# OSO-SWAT-A1-04-BLUE.net
KiCad netlist of a schematic drawn in EAGLE
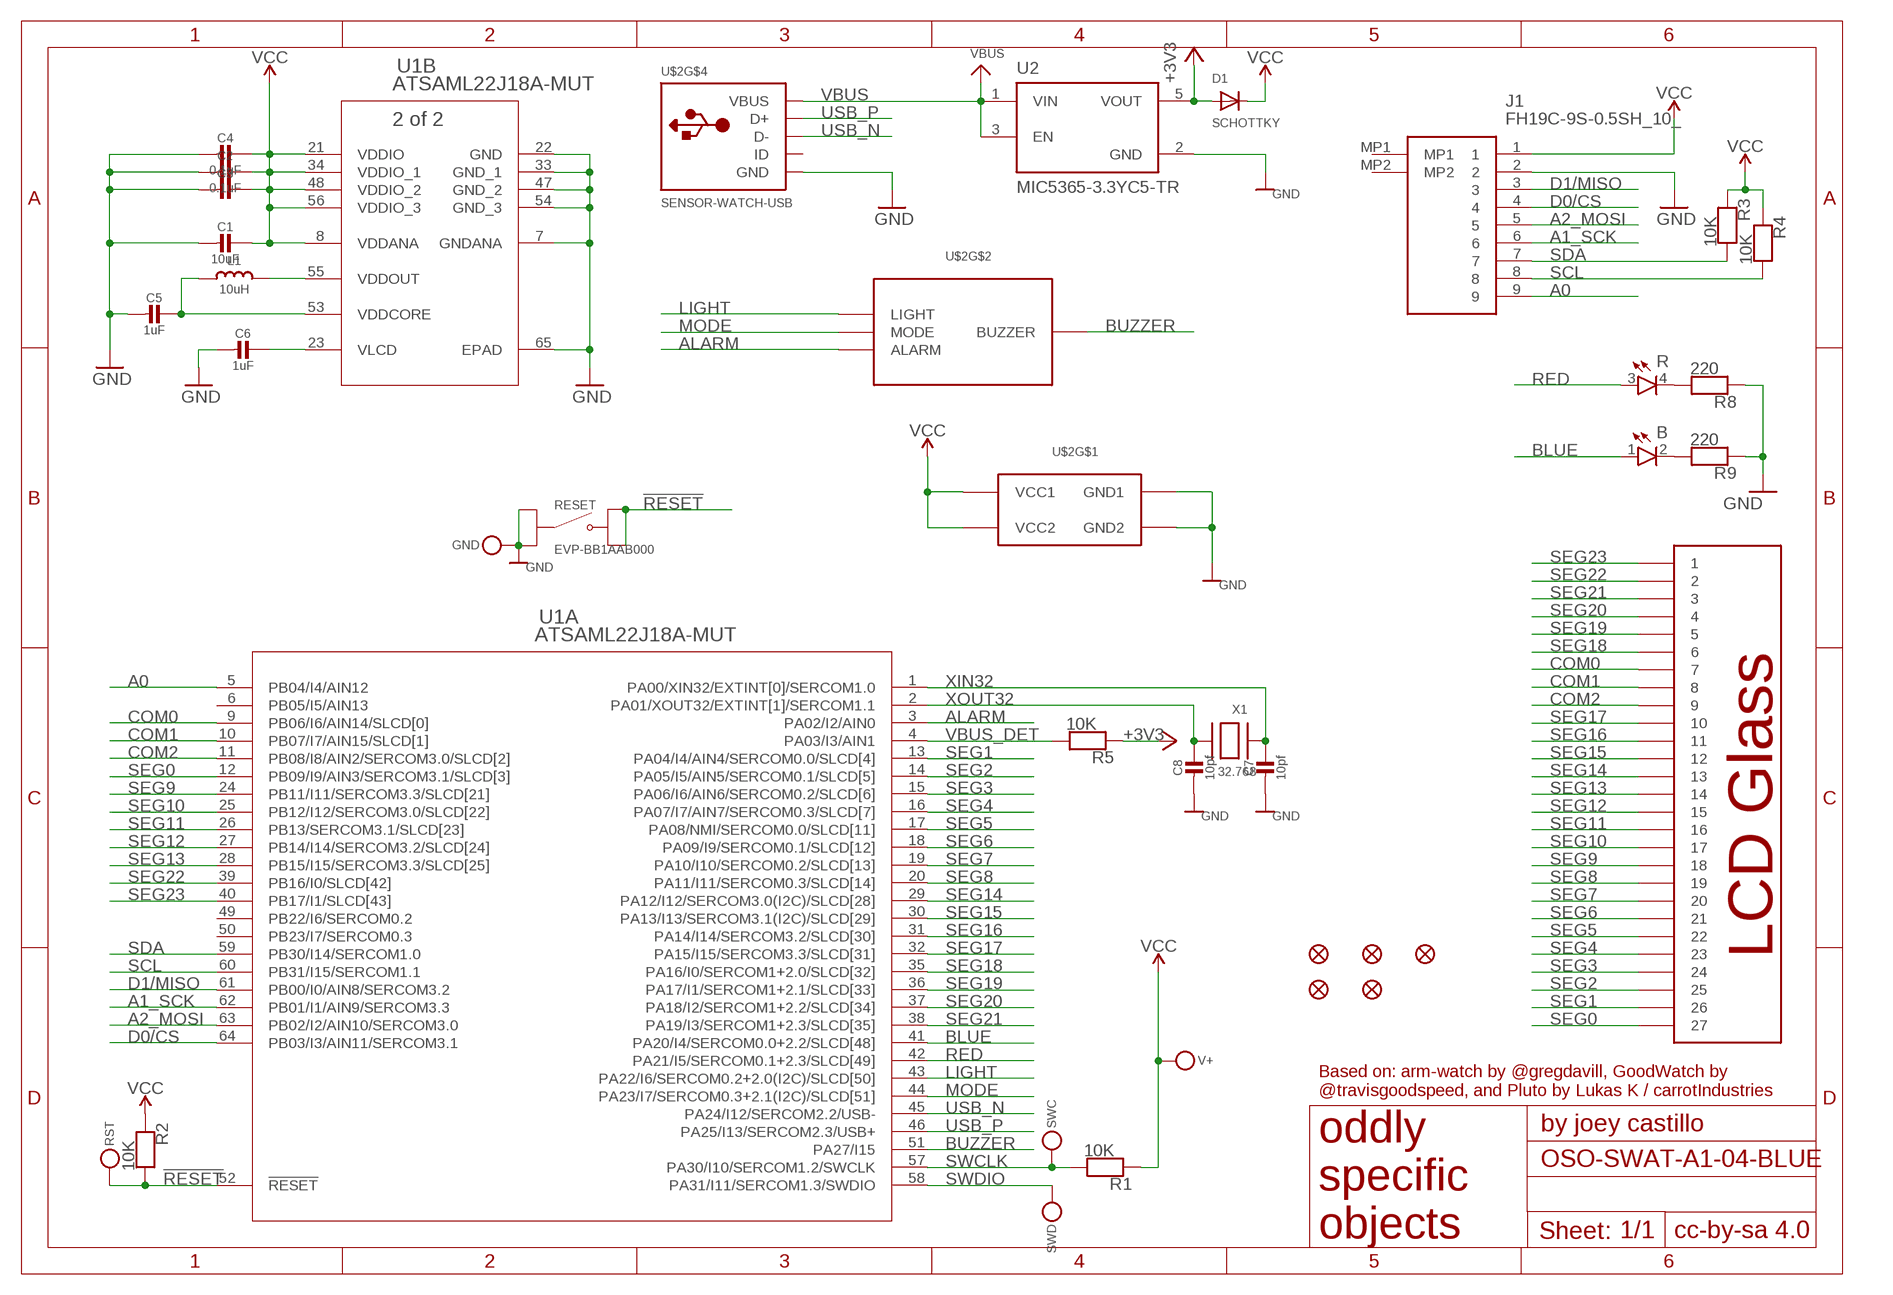
[diagram p0: schematic, sheet 1]

(export (version "E")
  (design (tool "Eeschema 10.0.6"))
  (components
    (comp (ref "C1")
      (value "10uF")
      (footprint "eagle-import:_0603MP")
      (libsource (lib "eagle-import") (part "CAP_CERAMIC_0603MP"))
    )
    (comp (ref "C2")
      (value "0.1uF")
      (footprint "eagle-import:_0603MP")
      (libsource (lib "eagle-import") (part "CAP_CERAMIC_0603MP"))
    )
    (comp (ref "C3")
      (value "0.1uF")
      (footprint "eagle-import:_0603MP")
      (libsource (lib "eagle-import") (part "CAP_CERAMIC_0603MP"))
    )
    (comp (ref "C4")
      (value "0.1uF")
      (footprint "eagle-import:_0603MP")
      (libsource (lib "eagle-import") (part "CAP_CERAMIC_0603MP"))
    )
    (comp (ref "C5")
      (value "1uF")
      (footprint "eagle-import:_0603MP")
      (libsource (lib "eagle-import") (part "CAP_CERAMIC_0603MP"))
    )
    (comp (ref "C6")
      (value "1uF")
      (footprint "eagle-import:_0603MP")
      (libsource (lib "eagle-import") (part "CAP_CERAMIC_0603MP"))
    )
    (comp (ref "C7")
      (value "10pf")
      (footprint "eagle-import:_0402MP")
      (libsource (lib "eagle-import") (part "CAP_CERAMIC_0402MP"))
    )
    (comp (ref "C8")
      (value "10pf")
      (footprint "eagle-import:_0402MP")
      (libsource (lib "eagle-import") (part "CAP_CERAMIC_0402MP"))
    )
    (comp (ref "D1")
      (value "SCHOTTKY")
      (footprint "eagle-import:SOD-323F")
      (libsource (lib "eagle-import") (part "DIODESOD-323F"))
    )
    (comp (ref "FID1")
      (value "FIDUCIAL_1MM")
      (footprint "eagle-import:FIDUCIAL_1MM")
      (libsource (lib "eagle-import") (part "FIDUCIAL_1MM"))
    )
    (comp (ref "FID2")
      (value "FIDUCIAL_1MM")
      (footprint "eagle-import:FIDUCIAL_1MM")
      (libsource (lib "eagle-import") (part "FIDUCIAL_1MM"))
    )
    (comp (ref "FID3")
      (value "FIDUCIAL_1MM")
      (footprint "eagle-import:FIDUCIAL_1MM")
      (fields (field (name "REV") "A"))
      (libsource (lib "eagle-import") (part "FIDUCIAL_1MM"))
    )
    (comp (ref "FID4")
      (value "FIDUCIAL_1MM")
      (footprint "eagle-import:FIDUCIAL_1MM")
      (libsource (lib "eagle-import") (part "FIDUCIAL_1MM"))
    )
    (comp (ref "FID6")
      (value "FIDUCIAL_1MM")
      (footprint "eagle-import:FIDUCIAL_1MM")
      (fields (field (name "REV") "A"))
      (libsource (lib "eagle-import") (part "FIDUCIAL_1MM"))
    )
    (comp (ref "GND")
      (value "MICROBUILDER_TESTPOINTROUND1.5MM")
      (footprint "eagle-import:MICROBUILDER_TESTPOINT_ROUND_1.5MM")
      (libsource (lib "eagle-import") (part "MICROBUILDER_TESTPOINTROUND1.5MM"))
    )
    (comp (ref "J1")
      (value "FH19C-9S-0.5SH_10_")
      (footprint "eagle-import:FH19C9S05SH10")
      (fields
        (field (name "MANUFACTURER_PART_NUMBER") "FH19C-9S-0.5SH(10)")
        (field (name "MOUSER_PART_NUMBER") "798-FH19C9S05SH10")
      )
      (libsource (lib "eagle-import") (part "FH19C-9S-0.5SH_10_"))
    )
    (comp (ref "L1")
      (value "10uH")
      (footprint "eagle-import:MICROBUILDER__0805MP")
      (libsource (lib "eagle-import") (part "MICROBUILDER_INDUCTOR_0805MP"))
    )
    (comp (ref "LED")
      (value "QBLP655-RIB")
      (footprint "eagle-import:LED_QBLP655")
      (fields
        (field (name "DIGI-KEY_PART_NUMBER") "160-2026-1-ND")
        (field (name "MF") "Lite-On Inc.")
        (field (name "MP") "LTST-C235KGKRKT")
      )
      (libsource (lib "eagle-import") (part "QBLP655-RIB"))
    )
    (comp (ref "R1")
      (value "10K")
      (footprint "eagle-import:_0603MP")
      (libsource (lib "eagle-import") (part "RESISTOR_0603MP"))
    )
    (comp (ref "R2")
      (value "10K")
      (footprint "eagle-import:_0603MP")
      (libsource (lib "eagle-import") (part "RESISTOR_0603MP"))
    )
    (comp (ref "R3")
      (value "10K")
      (footprint "eagle-import:_0603MP")
      (libsource (lib "eagle-import") (part "RESISTOR_0603MP"))
    )
    (comp (ref "R4")
      (value "10K")
      (footprint "eagle-import:_0603MP")
      (libsource (lib "eagle-import") (part "RESISTOR_0603MP"))
    )
    (comp (ref "R5")
      (value "10K")
      (footprint "eagle-import:_0603MP")
      (libsource (lib "eagle-import") (part "RESISTOR_0603MP"))
    )
    (comp (ref "R8")
      (value "220")
      (footprint "eagle-import:_0603MP")
      (libsource (lib "eagle-import") (part "RESISTOR_0603MP"))
    )
    (comp (ref "R9")
      (value "220")
      (footprint "eagle-import:_0603MP")
      (libsource (lib "eagle-import") (part "RESISTOR_0603MP"))
    )
    (comp (ref "RESET")
      (value "EVP-BB1AAB000")
      (footprint "eagle-import:SW_EVP-BB1AAB000")
      (fields
        (field (name "DIGI-KEY_PART_NUMBER") "P124390CT-ND")
        (field (name "MF") "Panasonic Electronic Components")
      )
      (libsource (lib "eagle-import") (part "EVP-BB1AAB000"))
    )
    (comp (ref "RST")
      (value "MICROBUILDER_TESTPOINTROUND1.5MM")
      (footprint "eagle-import:MICROBUILDER_TESTPOINT_ROUND_1.5MM")
      (libsource (lib "eagle-import") (part "MICROBUILDER_TESTPOINTROUND1.5MM"))
    )
    (comp (ref "SWC")
      (value "MICROBUILDER_TESTPOINTROUND1.5MM")
      (footprint "eagle-import:MICROBUILDER_TESTPOINT_ROUND_1.5MM")
      (libsource (lib "eagle-import") (part "MICROBUILDER_TESTPOINTROUND1.5MM"))
    )
    (comp (ref "SWD")
      (value "MICROBUILDER_TESTPOINTROUND1.5MM")
      (footprint "eagle-import:MICROBUILDER_TESTPOINT_ROUND_1.5MM")
      (libsource (lib "eagle-import") (part "MICROBUILDER_TESTPOINTROUND1.5MM"))
    )
    (comp (ref "U$2")
      (value "SENSOR-WATCH-USB")
      (footprint "eagle-import:CASIO-F91W-OUTLINE-USB")
      (libsource (lib "eagle-import") (part "SENSOR-WATCH-USB"))
    )
    (comp (ref "U1")
      (value "ATSAML22J18A-MUT")
      (footprint "eagle-import:QFN64_9X9MC_MCH")
      (fields (field (name "COPYRIGHT") "Copyright (C) 2018 Accelerated Designs. All rights reserved"))
      (libsource (lib "eagle-import") (part "ATSAML22J18A-MUT"))
    )
    (comp (ref "U2")
      (value "MIC5365-3.3YC5-TR")
      (footprint "eagle-import:SOT65P210X110-5N")
      (fields (field (name "DIGI-KEY_PART_NUMBER") "576-3193-1-ND") (field (name "MF") "Microchip"))
      (libsource (lib "eagle-import") (part "MIC5365-3.3YC5-TR"))
    )
    (comp (ref "V+")
      (value "MICROBUILDER_TESTPOINTROUND1.5MM")
      (footprint "eagle-import:MICROBUILDER_TESTPOINT_ROUND_1.5MM")
      (libsource (lib "eagle-import") (part "MICROBUILDER_TESTPOINTROUND1.5MM"))
    )
    (comp (ref "X1")
      (value "32.768")
      (footprint "eagle-import:XTAL3215")
      (libsource (lib "eagle-import") (part "XTAL-3.2X1.5"))
    )
  )
  (nets
    (net (code "1") (name "+3V3") (class "Default")
      (node (ref "D1") (pin "A") (pinfunction "A_A") (pintype "passive"))
      (node (ref "R5") (pin "1") (pinfunction "1_1") (pintype "passive"))
      (node (ref "U2") (pin "5") (pinfunction "VOUT_5") (pintype "output"))
    )
    (net (code "2") (name "/A0") (class "Default")
      (node (ref "J1") (pin "9") (pinfunction "9_9") (pintype "bidirectional"))
      (node (ref "U1") (pin "5") (pinfunction "PB04/I4/AIN12_5") (pintype "bidirectional"))
    )
    (net (code "3") (name "/A1_SCK") (class "Default")
      (node (ref "J1") (pin "6") (pinfunction "6_6") (pintype "bidirectional"))
      (node (ref "U1") (pin "62") (pinfunction "PB01/I1/AIN9/SERCOM3.3_62") (pintype "bidirectional"))
    )
    (net (code "4") (name "/A2_MOSI") (class "Default")
      (node (ref "J1") (pin "5") (pinfunction "5_5") (pintype "bidirectional"))
      (node (ref "U1") (pin "63") (pinfunction "PB02/I2/AIN10/SERCOM3.0_63") (pintype "bidirectional"))
    )
    (net (code "5") (name "/ALARM") (class "Default")
      (node (ref "U$2") (pin "ALARM") (pinfunction "ALARM_ALARM") (pintype "bidirectional"))
      (node (ref "U1") (pin "3") (pinfunction "PA02/I2/AIN0_3") (pintype "bidirectional"))
    )
    (net (code "6") (name "/BLUE") (class "Default")
      (node (ref "LED") (pin "1") (pinfunction "A_1") (pintype "passive"))
      (node (ref "U1") (pin "41") (pinfunction "PA20/I4/SERCOM0.0+2.2/SLCD[48]_41") (pintype "bidirectional"))
    )
    (net (code "7") (name "/BUZZER") (class "Default")
      (node (ref "U$2") (pin "BUZZER") (pinfunction "BUZZER_BUZZER") (pintype "bidirectional"))
      (node (ref "U1") (pin "51") (pinfunction "PA27/I15_51") (pintype "bidirectional"))
    )
    (net (code "8") (name "/COM0") (class "Default")
      (node (ref "U$2") (pin "7") (pinfunction "7_7") (pintype "input"))
      (node (ref "U1") (pin "9") (pinfunction "PB06/I6/AIN14/SLCD[0]_9") (pintype "bidirectional"))
    )
    (net (code "9") (name "/COM1") (class "Default")
      (node (ref "U$2") (pin "8") (pinfunction "8_8") (pintype "input"))
      (node (ref "U1") (pin "10") (pinfunction "PB07/I7/AIN15/SLCD[1]_10") (pintype "bidirectional"))
    )
    (net (code "10") (name "/COM2") (class "Default")
      (node (ref "U$2") (pin "9") (pinfunction "9_9") (pintype "input"))
      (node (ref "U1") (pin "11") (pinfunction "PB08/I8/AIN2/SERCOM3.0/SLCD[2]_11") (pintype "bidirectional"))
    )
    (net (code "11") (name "/D0{slash}CS") (class "Default")
      (node (ref "J1") (pin "4") (pinfunction "4_4") (pintype "bidirectional"))
      (node (ref "U1") (pin "64") (pinfunction "PB03/I3/AIN11/SERCOM3.1_64") (pintype "bidirectional"))
    )
    (net (code "12") (name "/D1{slash}MISO") (class "Default")
      (node (ref "J1") (pin "3") (pinfunction "3_3") (pintype "bidirectional"))
      (node (ref "U1") (pin "61") (pinfunction "PB00/I0/AIN8/SERCOM3.2_61") (pintype "bidirectional"))
    )
    (net (code "13") (name "/LIGHT") (class "Default")
      (node (ref "U$2") (pin "LIGHT") (pinfunction "LIGHT_LIGHT") (pintype "bidirectional"))
      (node (ref "U1") (pin "43") (pinfunction "PA22/I6/SERCOM0.2+2.0(I2C)/SLCD[50]_43") (pintype "bidirectional"))
    )
    (net (code "14") (name "/MODE") (class "Default")
      (node (ref "U$2") (pin "MODE") (pinfunction "MODE_MODE") (pintype "bidirectional"))
      (node (ref "U1") (pin "44") (pinfunction "PA23/I7/SERCOM0.3+2.1(I2C)/SLCD[51]_44") (pintype "bidirectional"))
    )
    (net (code "15") (name "/RED") (class "Default")
      (node (ref "LED") (pin "3") (pinfunction "A_3") (pintype "passive"))
      (node (ref "U1") (pin "42") (pinfunction "PA21/I5/SERCOM0.1+2.3/SLCD[49]_42") (pintype "bidirectional"))
    )
    (net (code "16") (name "/SCL") (class "Default")
      (node (ref "J1") (pin "8") (pinfunction "8_8") (pintype "bidirectional"))
      (node (ref "R4") (pin "2") (pinfunction "2_2") (pintype "passive"))
      (node (ref "U1") (pin "60") (pinfunction "PB31/I15/SERCOM1.1_60") (pintype "bidirectional"))
    )
    (net (code "17") (name "/SDA") (class "Default")
      (node (ref "J1") (pin "7") (pinfunction "7_7") (pintype "bidirectional"))
      (node (ref "R3") (pin "2") (pinfunction "2_2") (pintype "passive"))
      (node (ref "U1") (pin "59") (pinfunction "PB30/I14/SERCOM1.0_59") (pintype "bidirectional"))
    )
    (net (code "18") (name "/SEG0") (class "Default")
      (node (ref "U$2") (pin "27") (pinfunction "27_27") (pintype "input"))
      (node (ref "U1") (pin "12") (pinfunction "PB09/I9/AIN3/SERCOM3.1/SLCD[3]_12") (pintype "bidirectional"))
    )
    (net (code "19") (name "/SEG1") (class "Default")
      (node (ref "U$2") (pin "26") (pinfunction "26_26") (pintype "input"))
      (node (ref "U1") (pin "13") (pinfunction "PA04/I4/AIN4/SERCOM0.0/SLCD[4]_13") (pintype "bidirectional"))
    )
    (net (code "20") (name "/SEG2") (class "Default")
      (node (ref "U$2") (pin "25") (pinfunction "25_25") (pintype "input"))
      (node (ref "U1") (pin "14") (pinfunction "PA05/I5/AIN5/SERCOM0.1/SLCD[5]_14") (pintype "bidirectional"))
    )
    (net (code "21") (name "/SEG3") (class "Default")
      (node (ref "U$2") (pin "24") (pinfunction "24_24") (pintype "input"))
      (node (ref "U1") (pin "15") (pinfunction "PA06/I6/AIN6/SERCOM0.2/SLCD[6]_15") (pintype "bidirectional"))
    )
    (net (code "22") (name "/SEG4") (class "Default")
      (node (ref "U$2") (pin "23") (pinfunction "23_23") (pintype "input"))
      (node (ref "U1") (pin "16") (pinfunction "PA07/I7/AIN7/SERCOM0.3/SLCD[7]_16") (pintype "bidirectional"))
    )
    (net (code "23") (name "/SEG5") (class "Default")
      (node (ref "U$2") (pin "22") (pinfunction "22_22") (pintype "input"))
      (node (ref "U1") (pin "17") (pinfunction "PA08/NMI/SERCOM0.0/SLCD[11]_17") (pintype "bidirectional"))
    )
    (net (code "24") (name "/SEG6") (class "Default")
      (node (ref "U$2") (pin "21") (pinfunction "21_21") (pintype "input"))
      (node (ref "U1") (pin "18") (pinfunction "PA09/I9/SERCOM0.1/SLCD[12]_18") (pintype "bidirectional"))
    )
    (net (code "25") (name "/SEG7") (class "Default")
      (node (ref "U$2") (pin "20") (pinfunction "20_20") (pintype "input"))
      (node (ref "U1") (pin "19") (pinfunction "PA10/I10/SERCOM0.2/SLCD[13]_19") (pintype "bidirectional"))
    )
    (net (code "26") (name "/SEG8") (class "Default")
      (node (ref "U$2") (pin "19") (pinfunction "19_19") (pintype "input"))
      (node (ref "U1") (pin "20") (pinfunction "PA11/I11/SERCOM0.3/SLCD[14]_20") (pintype "bidirectional"))
    )
    (net (code "27") (name "/SEG9") (class "Default")
      (node (ref "U$2") (pin "18") (pinfunction "18_18") (pintype "input"))
      (node (ref "U1") (pin "24") (pinfunction "PB11/I11/SERCOM3.3/SLCD[21]_24") (pintype "bidirectional"))
    )
    (net (code "28") (name "/SEG10") (class "Default")
      (node (ref "U$2") (pin "17") (pinfunction "17_17") (pintype "input"))
      (node (ref "U1") (pin "25") (pinfunction "PB12/I12/SERCOM3.0/SLCD[22]_25") (pintype "bidirectional"))
    )
    (net (code "29") (name "/SEG11") (class "Default")
      (node (ref "U$2") (pin "16") (pinfunction "16_16") (pintype "input"))
      (node (ref "U1") (pin "26") (pinfunction "PB13/SERCOM3.1/SLCD[23]_26") (pintype "bidirectional"))
    )
    (net (code "30") (name "/SEG12") (class "Default")
      (node (ref "U$2") (pin "15") (pinfunction "15_15") (pintype "input"))
      (node (ref "U1") (pin "27") (pinfunction "PB14/I14/SERCOM3.2/SLCD[24]_27") (pintype "bidirectional"))
    )
    (net (code "31") (name "/SEG13") (class "Default")
      (node (ref "U$2") (pin "14") (pinfunction "14_14") (pintype "input"))
      (node (ref "U1") (pin "28") (pinfunction "PB15/I15/SERCOM3.3/SLCD[25]_28") (pintype "bidirectional"))
    )
    (net (code "32") (name "/SEG14") (class "Default")
      (node (ref "U$2") (pin "13") (pinfunction "13_13") (pintype "input"))
      (node (ref "U1") (pin "29") (pinfunction "PA12/I12/SERCOM3.0(I2C)/SLCD[28]_29") (pintype "bidirectional"))
    )
    (net (code "33") (name "/SEG15") (class "Default")
      (node (ref "U$2") (pin "12") (pinfunction "12_12") (pintype "input"))
      (node (ref "U1") (pin "30") (pinfunction "PA13/I13/SERCOM3.1(I2C)/SLCD[29]_30") (pintype "bidirectional"))
    )
    (net (code "34") (name "/SEG16") (class "Default")
      (node (ref "U$2") (pin "11") (pinfunction "11_11") (pintype "input"))
      (node (ref "U1") (pin "31") (pinfunction "PA14/I14/SERCOM3.2/SLCD[30]_31") (pintype "bidirectional"))
    )
    (net (code "35") (name "/SEG17") (class "Default")
      (node (ref "U$2") (pin "10") (pinfunction "10_10") (pintype "input"))
      (node (ref "U1") (pin "32") (pinfunction "PA15/I15/SERCOM3.3/SLCD[31]_32") (pintype "bidirectional"))
    )
    (net (code "36") (name "/SEG18") (class "Default")
      (node (ref "U$2") (pin "6") (pinfunction "6_6") (pintype "input"))
      (node (ref "U1") (pin "35") (pinfunction "PA16/I0/SERCOM1+2.0/SLCD[32]_35") (pintype "bidirectional"))
    )
    (net (code "37") (name "/SEG19") (class "Default")
      (node (ref "U$2") (pin "5") (pinfunction "5_5") (pintype "input"))
      (node (ref "U1") (pin "36") (pinfunction "PA17/I1/SERCOM1+2.1/SLCD[33]_36") (pintype "bidirectional"))
    )
    (net (code "38") (name "/SEG20") (class "Default")
      (node (ref "U$2") (pin "4") (pinfunction "4_4") (pintype "input"))
      (node (ref "U1") (pin "37") (pinfunction "PA18/I2/SERCOM1+2.2/SLCD[34]_37") (pintype "bidirectional"))
    )
    (net (code "39") (name "/SEG21") (class "Default")
      (node (ref "U$2") (pin "3") (pinfunction "3_3") (pintype "input"))
      (node (ref "U1") (pin "38") (pinfunction "PA19/I3/SERCOM1+2.3/SLCD[35]_38") (pintype "bidirectional"))
    )
    (net (code "40") (name "/SEG22") (class "Default")
      (node (ref "U$2") (pin "2") (pinfunction "2_2") (pintype "input"))
      (node (ref "U1") (pin "39") (pinfunction "PB16/I0/SLCD[42]_39") (pintype "bidirectional"))
    )
    (net (code "41") (name "/SEG23") (class "Default")
      (node (ref "U$2") (pin "1") (pinfunction "1_1") (pintype "input"))
      (node (ref "U1") (pin "40") (pinfunction "PB17/I1/SLCD[43]_40") (pintype "bidirectional"))
    )
    (net (code "42") (name "/SWCLK") (class "Default")
      (node (ref "R1") (pin "2") (pinfunction "2_2") (pintype "passive"))
      (node (ref "SWC") (pin "P$1") (pinfunction "P$1_P$1") (pintype "bidirectional"))
      (node (ref "U1") (pin "57") (pinfunction "PA30/I10/SERCOM1.2/SWCLK_57") (pintype "bidirectional"))
    )
    (net (code "43") (name "/SWDIO") (class "Default")
      (node (ref "SWD") (pin "P$1") (pinfunction "P$1_P$1") (pintype "bidirectional"))
      (node (ref "U1") (pin "58") (pinfunction "PA31/I11/SERCOM1.3/SWDIO_58") (pintype "bidirectional"))
    )
    (net (code "44") (name "/USB_N") (class "Default")
      (node (ref "U$2") (pin "USB_N") (pinfunction "D-_USB_N") (pintype "bidirectional"))
      (node (ref "U1") (pin "45") (pinfunction "PA24/I12/SERCOM2.2/USB-_45") (pintype "bidirectional"))
    )
    (net (code "45") (name "/USB_P") (class "Default")
      (node (ref "U$2") (pin "USB_P") (pinfunction "D+_USB_P") (pintype "bidirectional"))
      (node (ref "U1") (pin "46") (pinfunction "PA25/I13/SERCOM2.3/USB+_46") (pintype "bidirectional"))
    )
    (net (code "46") (name "/VBUS_DET") (class "Default")
      (node (ref "R5") (pin "2") (pinfunction "2_2") (pintype "passive"))
      (node (ref "U1") (pin "4") (pinfunction "PA03/I3/AIN1_4") (pintype "bidirectional"))
    )
    (net (code "47") (name "/XIN32") (class "Default")
      (node (ref "C7") (pin "1") (pinfunction "1_1") (pintype "passive"))
      (node (ref "U1") (pin "1") (pinfunction "PA00/XIN32/EXTINT[0]/SERCOM1.0_1") (pintype "bidirectional"))
      (node (ref "X1") (pin "P$1") (pinfunction "P$1_P$1") (pintype "bidirectional"))
    )
    (net (code "48") (name "/XOUT32") (class "Default")
      (node (ref "C8") (pin "1") (pinfunction "1_1") (pintype "passive"))
      (node (ref "U1") (pin "2") (pinfunction "PA01/XOUT32/EXTINT[1]/SERCOM1.1_2") (pintype "bidirectional"))
      (node (ref "X1") (pin "P$2") (pinfunction "P$2_P$2") (pintype "bidirectional"))
    )
    (net (code "49") (name "/~{RESET}") (class "Default")
      (node (ref "R2") (pin "2") (pinfunction "2_2") (pintype "passive"))
      (node (ref "RESET") (pin "B1") (pinfunction "B1_B1") (pintype "passive"))
      (node (ref "RESET") (pin "B2") (pinfunction "B2_B2") (pintype "passive"))
      (node (ref "RST") (pin "P$1") (pinfunction "P$1_P$1") (pintype "bidirectional"))
      (node (ref "U1") (pin "52") (pinfunction "~{RESET}_52") (pintype "bidirectional"))
    )
    (net (code "50") (name "GND") (class "Default")
      (node (ref "C1") (pin "2") (pinfunction "2_2") (pintype "passive"))
      (node (ref "C2") (pin "2") (pinfunction "2_2") (pintype "passive"))
      (node (ref "C3") (pin "2") (pinfunction "2_2") (pintype "passive"))
      (node (ref "C4") (pin "2") (pinfunction "2_2") (pintype "passive"))
      (node (ref "C5") (pin "2") (pinfunction "2_2") (pintype "passive"))
      (node (ref "C6") (pin "2") (pinfunction "2_2") (pintype "passive"))
      (node (ref "C7") (pin "2") (pinfunction "2_2") (pintype "passive"))
      (node (ref "C8") (pin "2") (pinfunction "2_2") (pintype "passive"))
      (node (ref "GND") (pin "P$1") (pinfunction "P$1_P$1") (pintype "bidirectional"))
      (node (ref "J1") (pin "2") (pinfunction "2_2") (pintype "bidirectional"))
      (node (ref "R8") (pin "1") (pinfunction "1_1") (pintype "passive"))
      (node (ref "R9") (pin "1") (pinfunction "1_1") (pintype "passive"))
      (node (ref "RESET") (pin "A1") (pinfunction "A1_A1") (pintype "passive"))
      (node (ref "RESET") (pin "A2") (pinfunction "A2_A2") (pintype "passive"))
      (node (ref "U$2") (pin "GND") (pinfunction "GND_GND") (pintype "power_in"))
      (node (ref "U$2") (pin "GND1") (pinfunction "GND1_GND1") (pintype "bidirectional"))
      (node (ref "U$2") (pin "GND2") (pinfunction "GND2_GND2") (pintype "bidirectional"))
      (node (ref "U1") (pin "22") (pinfunction "GND_22") (pintype "passive"))
      (node (ref "U1") (pin "33") (pinfunction "GND_1_33") (pintype "passive"))
      (node (ref "U1") (pin "47") (pinfunction "GND_2_47") (pintype "passive"))
      (node (ref "U1") (pin "54") (pinfunction "GND_3_54") (pintype "passive"))
      (node (ref "U1") (pin "65") (pinfunction "EPAD_65") (pintype "passive"))
      (node (ref "U1") (pin "7") (pinfunction "GNDANA_7") (pintype "passive"))
      (node (ref "U2") (pin "2") (pinfunction "GND_2") (pintype "power_in"))
    )
    (net (code "51") (name "Net-(LEDA-C)") (class "Default")
      (node (ref "LED") (pin "2") (pinfunction "C_2") (pintype "passive"))
      (node (ref "R9") (pin "2") (pinfunction "2_2") (pintype "passive"))
    )
    (net (code "52") (name "Net-(LEDB-C)") (class "Default")
      (node (ref "LED") (pin "4") (pinfunction "C_4") (pintype "passive"))
      (node (ref "R8") (pin "2") (pinfunction "2_2") (pintype "passive"))
    )
    (net (code "53") (name "Net-(U1B-VDDCORE)") (class "Default")
      (node (ref "C5") (pin "1") (pinfunction "1_1") (pintype "passive"))
      (node (ref "L1") (pin "1") (pinfunction "1_1") (pintype "passive"))
      (node (ref "U1") (pin "53") (pinfunction "VDDCORE_53") (pintype "power_in"))
    )
    (net (code "54") (name "Net-(U1B-VDDOUT)") (class "Default")
      (node (ref "L1") (pin "2") (pinfunction "2_2") (pintype "passive"))
      (node (ref "U1") (pin "55") (pinfunction "VDDOUT_55") (pintype "output"))
    )
    (net (code "55") (name "Net-(U1B-VLCD)") (class "Default")
      (node (ref "C6") (pin "1") (pinfunction "1_1") (pintype "passive"))
      (node (ref "U1") (pin "23") (pinfunction "VLCD_23") (pintype "passive"))
    )
    (net (code "56") (name "VBUS") (class "Default")
      (node (ref "U$2") (pin "VBUS") (pinfunction "VBUS_VBUS") (pintype "power_in"))
      (node (ref "U2") (pin "1") (pinfunction "VIN_1") (pintype "input"))
      (node (ref "U2") (pin "3") (pinfunction "EN_3") (pintype "input"))
    )
    (net (code "57") (name "VCC") (class "Default")
      (node (ref "C1") (pin "1") (pinfunction "1_1") (pintype "passive"))
      (node (ref "C2") (pin "1") (pinfunction "1_1") (pintype "passive"))
      (node (ref "C3") (pin "1") (pinfunction "1_1") (pintype "passive"))
      (node (ref "C4") (pin "1") (pinfunction "1_1") (pintype "passive"))
      (node (ref "D1") (pin "C") (pinfunction "C_C") (pintype "passive"))
      (node (ref "J1") (pin "1") (pinfunction "1_1") (pintype "bidirectional"))
      (node (ref "R1") (pin "1") (pinfunction "1_1") (pintype "passive"))
      (node (ref "R2") (pin "1") (pinfunction "1_1") (pintype "passive"))
      (node (ref "R3") (pin "1") (pinfunction "1_1") (pintype "passive"))
      (node (ref "R4") (pin "1") (pinfunction "1_1") (pintype "passive"))
      (node (ref "U$2") (pin "VCC1") (pinfunction "VCC1_VCC1") (pintype "bidirectional"))
      (node (ref "U$2") (pin "VCC2") (pinfunction "VCC2_VCC2") (pintype "bidirectional"))
      (node (ref "U1") (pin "21") (pinfunction "VDDIO_21") (pintype "power_in"))
      (node (ref "U1") (pin "34") (pinfunction "VDDIO_1_34") (pintype "power_in"))
      (node (ref "U1") (pin "48") (pinfunction "VDDIO_2_48") (pintype "power_in"))
      (node (ref "U1") (pin "56") (pinfunction "VDDIO_3_56") (pintype "power_in"))
      (node (ref "U1") (pin "8") (pinfunction "VDDANA_8") (pintype "power_in"))
      (node (ref "V+") (pin "P$1") (pinfunction "P$1_P$1") (pintype "bidirectional"))
    )
    (net (code "58") (name "unconnected-(J1-PadMP1)") (class "Default")
      (node (ref "J1") (pin "MP1") (pinfunction "MP1_MP1") (pintype "bidirectional"))
    )
    (net (code "59") (name "unconnected-(J1-PadMP2)") (class "Default")
      (node (ref "J1") (pin "MP2") (pinfunction "MP2_MP2") (pintype "bidirectional"))
    )
    (net (code "60") (name "unconnected-(U$2D-ID-PadUSB_ID)") (class "Default")
      (node (ref "U$2") (pin "USB_ID") (pinfunction "ID_USB_ID") (pintype "bidirectional"))
    )
    (net (code "61") (name "unconnected-(U1A-PB05{slash}I5{slash}AIN13-Pad6)") (class "Default")
      (node (ref "U1") (pin "6") (pinfunction "PB05/I5/AIN13_6") (pintype "bidirectional"))
    )
    (net (code "62") (name "unconnected-(U1A-PB22{slash}I6{slash}SERCOM0.2-Pad49)") (class "Default")
      (node (ref "U1") (pin "49") (pinfunction "PB22/I6/SERCOM0.2_49") (pintype "bidirectional"))
    )
    (net (code "63") (name "unconnected-(U1A-PB23{slash}I7{slash}SERCOM0.3-Pad50)") (class "Default")
      (node (ref "U1") (pin "50") (pinfunction "PB23/I7/SERCOM0.3_50") (pintype "bidirectional"))
    )
  )
)
